# Regolatori_ua78xx.net
KiCad netlist of a schematic drawn in EAGLE
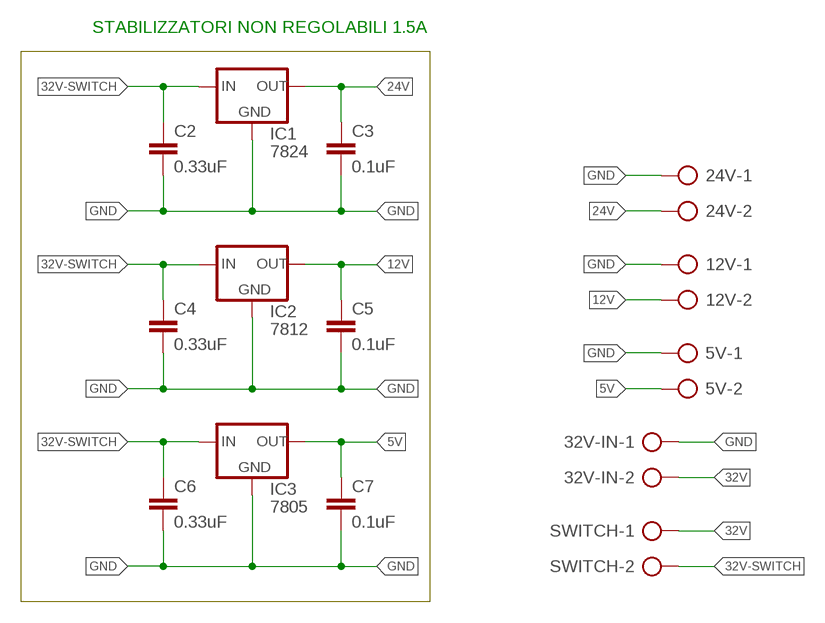
[diagram p0: schematic, sheet 1]

(export (version "E")
  (design (tool "Eeschema 10.0.6"))
  (components
    (comp (ref "5V")
      (value "SMKDSP_1,5/2")
      (footprint "eagle-import:SMKDSP_1,5_2")
      (fields (field (name "MF") "FARNELL") (field (name "MPN") "1733570"))
      (libsource (lib "eagle-import") (part "SMKDSP_1,5/2"))
    )
    (comp (ref "12V")
      (value "SMKDSP_1,5/2")
      (footprint "eagle-import:SMKDSP_1,5_2")
      (fields (field (name "MF") "FARNELL") (field (name "MPN") "1733570"))
      (libsource (lib "eagle-import") (part "SMKDSP_1,5/2"))
    )
    (comp (ref "24V")
      (value "SMKDSP_1,5/2")
      (footprint "eagle-import:SMKDSP_1,5_2")
      (fields (field (name "MF") "FARNELL") (field (name "MPN") "1733570"))
      (libsource (lib "eagle-import") (part "SMKDSP_1,5/2"))
    )
    (comp (ref "32V-IN")
      (value "SMKDSP_1,5/2")
      (footprint "eagle-import:SMKDSP_1,5_2")
      (fields (field (name "MF") "FARNELL") (field (name "MPN") "1733570"))
      (libsource (lib "eagle-import") (part "SMKDSP_1,5/2"))
    )
    (comp (ref "C2")
      (value "0.33uF")
      (footprint "eagle-import:C025-025X050")
      (libsource (lib "eagle-import") (part "C-EU025-025X050"))
    )
    (comp (ref "C3")
      (value "0.1uF")
      (footprint "eagle-import:C025-025X050")
      (libsource (lib "eagle-import") (part "C-EU025-025X050"))
    )
    (comp (ref "C4")
      (value "0.33uF")
      (footprint "eagle-import:C025-025X050")
      (libsource (lib "eagle-import") (part "C-EU025-025X050"))
    )
    (comp (ref "C5")
      (value "0.1uF")
      (footprint "eagle-import:C025-025X050")
      (libsource (lib "eagle-import") (part "C-EU025-025X050"))
    )
    (comp (ref "C6")
      (value "0.33uF")
      (footprint "eagle-import:C025-025X050")
      (libsource (lib "eagle-import") (part "C-EU025-025X050"))
    )
    (comp (ref "C7")
      (value "0.1uF")
      (footprint "eagle-import:C025-025X050")
      (libsource (lib "eagle-import") (part "C-EU025-025X050"))
    )
    (comp (ref "IC1")
      (value "7824")
      (footprint "eagle-import:78XXS")
      (libsource (lib "eagle-import") (part "78XXS"))
    )
    (comp (ref "IC2")
      (value "7812")
      (footprint "eagle-import:78XXS")
      (libsource (lib "eagle-import") (part "78XXS"))
    )
    (comp (ref "IC3")
      (value "7805")
      (footprint "eagle-import:78XXS")
      (libsource (lib "eagle-import") (part "78XXS"))
    )
    (comp (ref "SWITCH")
      (value "SMKDSP_1,5/2")
      (footprint "eagle-import:SMKDSP_1,5_2")
      (fields (field (name "MF") "FARNELL") (field (name "MPN") "1733570"))
      (libsource (lib "eagle-import") (part "SMKDSP_1,5/2"))
    )
  )
  (nets
    (net (code "1") (name "5V") (class "Default")
      (node (ref "5V") (pin "2") (pinfunction "KL_2") (pintype "passive"))
      (node (ref "C7") (pin "1") (pinfunction "1_1") (pintype "passive"))
      (node (ref "IC3") (pin "OUT") (pinfunction "OUT_OUT") (pintype "passive"))
    )
    (net (code "2") (name "12V") (class "Default")
      (node (ref "12V") (pin "2") (pinfunction "KL_2") (pintype "passive"))
      (node (ref "C5") (pin "1") (pinfunction "1_1") (pintype "passive"))
      (node (ref "IC2") (pin "OUT") (pinfunction "OUT_OUT") (pintype "passive"))
    )
    (net (code "3") (name "24V") (class "Default")
      (node (ref "24V") (pin "2") (pinfunction "KL_2") (pintype "passive"))
      (node (ref "C3") (pin "1") (pinfunction "1_1") (pintype "passive"))
      (node (ref "IC1") (pin "OUT") (pinfunction "OUT_OUT") (pintype "passive"))
    )
    (net (code "4") (name "32V") (class "Default")
      (node (ref "32V-IN") (pin "2") (pinfunction "KL_2") (pintype "passive"))
      (node (ref "SWITCH") (pin "1") (pinfunction "KL_1") (pintype "passive"))
    )
    (net (code "5") (name "32V-SWITCH") (class "Default")
      (node (ref "C2") (pin "1") (pinfunction "1_1") (pintype "passive"))
      (node (ref "C4") (pin "1") (pinfunction "1_1") (pintype "passive"))
      (node (ref "C6") (pin "1") (pinfunction "1_1") (pintype "passive"))
      (node (ref "IC1") (pin "IN") (pinfunction "IN_IN") (pintype "input"))
      (node (ref "IC2") (pin "IN") (pinfunction "IN_IN") (pintype "input"))
      (node (ref "IC3") (pin "IN") (pinfunction "IN_IN") (pintype "input"))
      (node (ref "SWITCH") (pin "2") (pinfunction "KL_2") (pintype "passive"))
    )
    (net (code "6") (name "GND") (class "Default")
      (node (ref "12V") (pin "1") (pinfunction "KL_1") (pintype "passive"))
      (node (ref "24V") (pin "1") (pinfunction "KL_1") (pintype "passive"))
      (node (ref "32V-IN") (pin "1") (pinfunction "KL_1") (pintype "passive"))
      (node (ref "5V") (pin "1") (pinfunction "KL_1") (pintype "passive"))
      (node (ref "C2") (pin "2") (pinfunction "2_2") (pintype "passive"))
      (node (ref "C3") (pin "2") (pinfunction "2_2") (pintype "passive"))
      (node (ref "C4") (pin "2") (pinfunction "2_2") (pintype "passive"))
      (node (ref "C5") (pin "2") (pinfunction "2_2") (pintype "passive"))
      (node (ref "C6") (pin "2") (pinfunction "2_2") (pintype "passive"))
      (node (ref "C7") (pin "2") (pinfunction "2_2") (pintype "passive"))
      (node (ref "IC1") (pin "GND") (pinfunction "GND_GND") (pintype "input"))
      (node (ref "IC2") (pin "GND") (pinfunction "GND_GND") (pintype "input"))
      (node (ref "IC3") (pin "GND") (pinfunction "GND_GND") (pintype "input"))
    )
  )
)
